# main.net
KiCad netlist of a schematic drawn in EAGLE
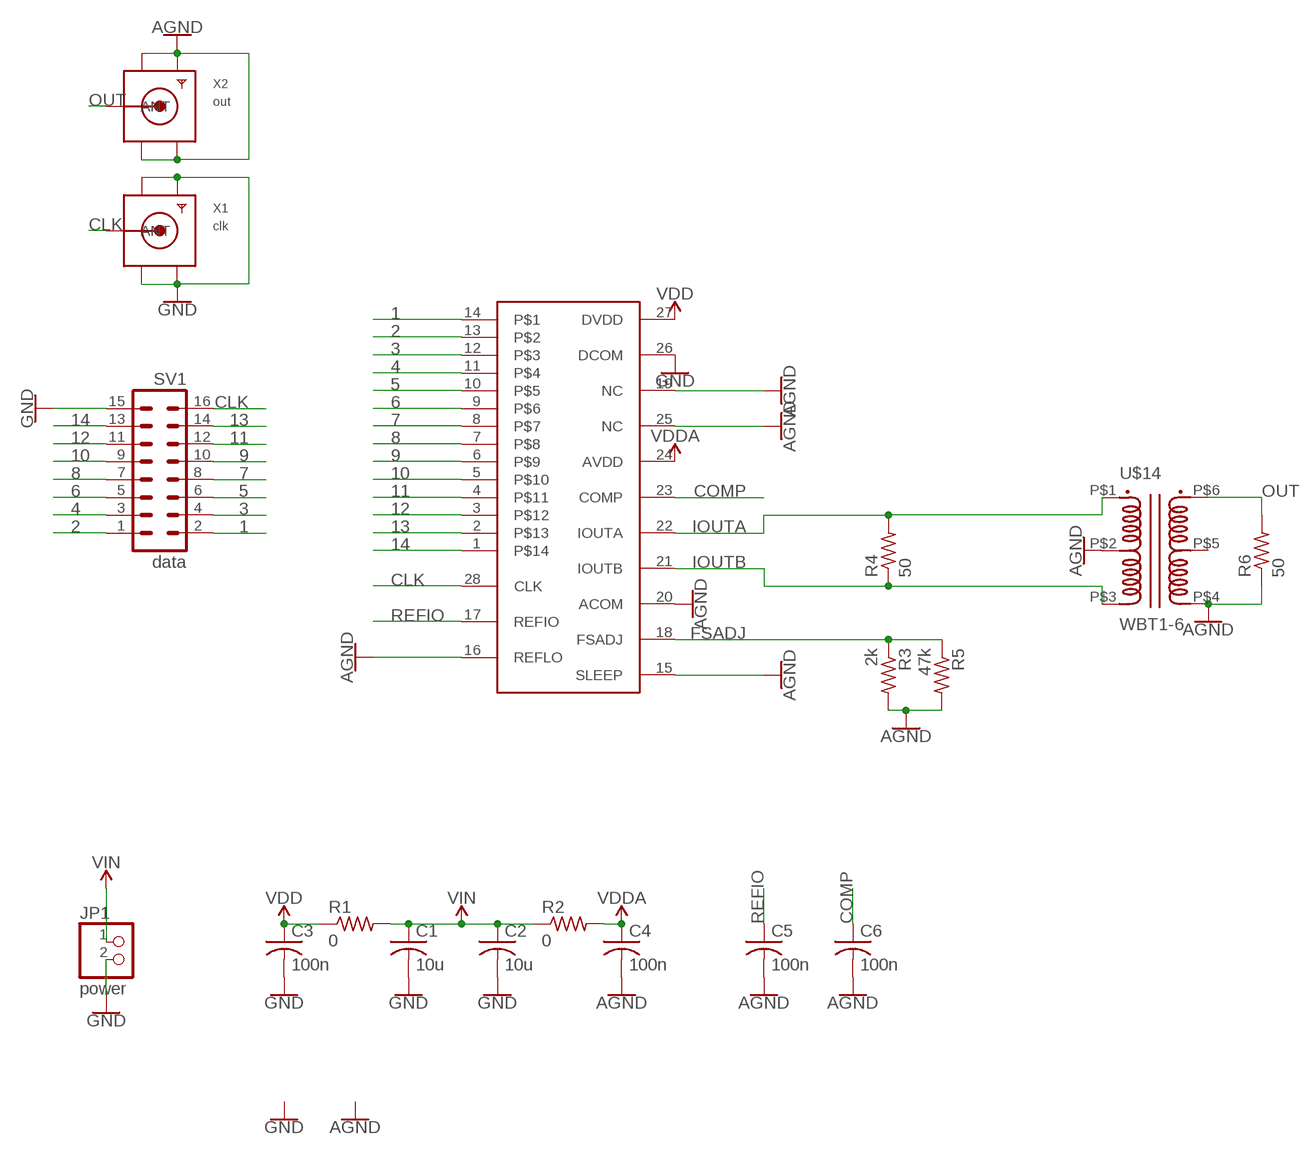
[diagram p0: schematic, sheet 1]

(export (version "E")
  (design (tool "Eeschema 10.0.6"))
  (components
    (comp (ref "C1")
      (value "10u")
      (footprint "eagle-import:C0805K")
      (libsource (lib "eagle-import") (part "C-USC0805K"))
    )
    (comp (ref "C2")
      (value "10u")
      (footprint "eagle-import:C0805K")
      (libsource (lib "eagle-import") (part "C-USC0805K"))
    )
    (comp (ref "C3")
      (value "100n")
      (footprint "eagle-import:C0603K")
      (libsource (lib "eagle-import") (part "C-USC0603K"))
    )
    (comp (ref "C4")
      (value "100n")
      (footprint "eagle-import:C0603K")
      (libsource (lib "eagle-import") (part "C-USC0603K"))
    )
    (comp (ref "C5")
      (value "100n")
      (footprint "eagle-import:C0603K")
      (libsource (lib "eagle-import") (part "C-USC0603K"))
    )
    (comp (ref "C6")
      (value "100n")
      (footprint "eagle-import:C0603K")
      (libsource (lib "eagle-import") (part "C-USC0603K"))
    )
    (comp (ref "JP1")
      (value "power")
      (footprint "eagle-import:1X02")
      (libsource (lib "eagle-import") (part "PINHD-1X2"))
    )
    (comp (ref "R1")
      (value "0")
      (footprint "eagle-import:0309_10")
      (libsource (lib "eagle-import") (part "R-US_0309/10"))
    )
    (comp (ref "R2")
      (value "0")
      (footprint "eagle-import:0309_10")
      (libsource (lib "eagle-import") (part "R-US_0309/10"))
    )
    (comp (ref "R3")
      (value "2k")
      (footprint "eagle-import:R0603")
      (libsource (lib "eagle-import") (part "R-US_R0603"))
    )
    (comp (ref "R4")
      (value "50")
      (footprint "eagle-import:R0603")
      (libsource (lib "eagle-import") (part "R-US_R0603"))
    )
    (comp (ref "R5")
      (value "47k")
      (footprint "eagle-import:R0603")
      (libsource (lib "eagle-import") (part "R-US_R0603"))
    )
    (comp (ref "R6")
      (value "50")
      (footprint "eagle-import:R0603")
      (libsource (lib "eagle-import") (part "R-US_R0603"))
    )
    (comp (ref "SV1")
      (value "data")
      (footprint "eagle-import:MA08-2")
      (libsource (lib "eagle-import") (part "MA08-2"))
    )
    (comp (ref "U$1")
      (value "ISL5961")
      (footprint "eagle-import:TSSOP28")
      (libsource (lib "eagle-import") (part "ISL5961"))
    )
    (comp (ref "U$14")
      (value "WBT1-6")
      (footprint "eagle-import:WBT1-6")
      (libsource (lib "eagle-import") (part "WBT1-6"))
    )
    (comp (ref "X1")
      (value "clk")
      (footprint "eagle-import:SMA_EDGELAUNCH")
      (libsource (lib "eagle-import") (part "SMACONNECTOR_EDGE"))
    )
    (comp (ref "X2")
      (value "out")
      (footprint "eagle-import:SMA_EDGELAUNCH")
      (libsource (lib "eagle-import") (part "SMACONNECTOR_EDGE"))
    )
  )
  (nets
    (net (code "1") (name "/1") (class "Default")
      (node (ref "SV1") (pin "2") (pinfunction "2_2") (pintype "passive"))
      (node (ref "U$1") (pin "14") (pinfunction "P$1_14") (pintype "bidirectional"))
    )
    (net (code "2") (name "/2") (class "Default")
      (node (ref "SV1") (pin "1") (pinfunction "1_1") (pintype "passive"))
      (node (ref "U$1") (pin "13") (pinfunction "P$2_13") (pintype "bidirectional"))
    )
    (net (code "3") (name "/3") (class "Default")
      (node (ref "SV1") (pin "4") (pinfunction "4_4") (pintype "passive"))
      (node (ref "U$1") (pin "12") (pinfunction "P$3_12") (pintype "bidirectional"))
    )
    (net (code "4") (name "/4") (class "Default")
      (node (ref "SV1") (pin "3") (pinfunction "3_3") (pintype "passive"))
      (node (ref "U$1") (pin "11") (pinfunction "P$4_11") (pintype "bidirectional"))
    )
    (net (code "5") (name "/5") (class "Default")
      (node (ref "SV1") (pin "6") (pinfunction "6_6") (pintype "passive"))
      (node (ref "U$1") (pin "10") (pinfunction "P$5_10") (pintype "bidirectional"))
    )
    (net (code "6") (name "/6") (class "Default")
      (node (ref "SV1") (pin "5") (pinfunction "5_5") (pintype "passive"))
      (node (ref "U$1") (pin "9") (pinfunction "P$6_9") (pintype "bidirectional"))
    )
    (net (code "7") (name "/7") (class "Default")
      (node (ref "SV1") (pin "8") (pinfunction "8_8") (pintype "passive"))
      (node (ref "U$1") (pin "8") (pinfunction "P$7_8") (pintype "bidirectional"))
    )
    (net (code "8") (name "/8") (class "Default")
      (node (ref "SV1") (pin "7") (pinfunction "7_7") (pintype "passive"))
      (node (ref "U$1") (pin "7") (pinfunction "P$8_7") (pintype "bidirectional"))
    )
    (net (code "9") (name "/9") (class "Default")
      (node (ref "SV1") (pin "10") (pinfunction "10_10") (pintype "passive"))
      (node (ref "U$1") (pin "6") (pinfunction "P$9_6") (pintype "bidirectional"))
    )
    (net (code "10") (name "/10") (class "Default")
      (node (ref "SV1") (pin "9") (pinfunction "9_9") (pintype "passive"))
      (node (ref "U$1") (pin "5") (pinfunction "P$10_5") (pintype "bidirectional"))
    )
    (net (code "11") (name "/11") (class "Default")
      (node (ref "SV1") (pin "12") (pinfunction "12_12") (pintype "passive"))
      (node (ref "U$1") (pin "4") (pinfunction "P$11_4") (pintype "bidirectional"))
    )
    (net (code "12") (name "/12") (class "Default")
      (node (ref "SV1") (pin "11") (pinfunction "11_11") (pintype "passive"))
      (node (ref "U$1") (pin "3") (pinfunction "P$12_3") (pintype "bidirectional"))
    )
    (net (code "13") (name "/13") (class "Default")
      (node (ref "SV1") (pin "14") (pinfunction "14_14") (pintype "passive"))
      (node (ref "U$1") (pin "2") (pinfunction "P$13_2") (pintype "bidirectional"))
    )
    (net (code "14") (name "/14") (class "Default")
      (node (ref "SV1") (pin "13") (pinfunction "13_13") (pintype "passive"))
      (node (ref "U$1") (pin "1") (pinfunction "P$14_1") (pintype "bidirectional"))
    )
    (net (code "15") (name "/CLK") (class "Default")
      (node (ref "SV1") (pin "16") (pinfunction "16_16") (pintype "passive"))
      (node (ref "U$1") (pin "28") (pinfunction "CLK_28") (pintype "bidirectional"))
      (node (ref "X1") (pin "P") (pinfunction "ANT_P") (pintype "bidirectional"))
    )
    (net (code "16") (name "/COMP") (class "Default")
      (node (ref "C6") (pin "1") (pinfunction "1_1") (pintype "passive"))
      (node (ref "U$1") (pin "23") (pinfunction "COMP_23") (pintype "bidirectional"))
    )
    (net (code "17") (name "/FSADJ") (class "Default")
      (node (ref "R3") (pin "1") (pinfunction "1_1") (pintype "passive"))
      (node (ref "R5") (pin "1") (pinfunction "1_1") (pintype "passive"))
      (node (ref "U$1") (pin "18") (pinfunction "FSADJ_18") (pintype "bidirectional"))
    )
    (net (code "18") (name "/IOUTA") (class "Default")
      (node (ref "R4") (pin "2") (pinfunction "2_2") (pintype "passive"))
      (node (ref "U$1") (pin "22") (pinfunction "IOUTA_22") (pintype "bidirectional"))
      (node (ref "U$14") (pin "P$1") (pinfunction "1A_P$1") (pintype "passive"))
    )
    (net (code "19") (name "/IOUTB") (class "Default")
      (node (ref "R4") (pin "1") (pinfunction "1_1") (pintype "passive"))
      (node (ref "U$1") (pin "21") (pinfunction "IOUTB_21") (pintype "bidirectional"))
      (node (ref "U$14") (pin "P$3") (pinfunction "1B_P$3") (pintype "passive"))
    )
    (net (code "20") (name "/OUT") (class "Default")
      (node (ref "R6") (pin "2") (pinfunction "2_2") (pintype "passive"))
      (node (ref "U$14") (pin "P$6") (pinfunction "2A_P$6") (pintype "passive"))
      (node (ref "X2") (pin "P") (pinfunction "ANT_P") (pintype "bidirectional"))
    )
    (net (code "21") (name "/REFIO") (class "Default")
      (node (ref "C5") (pin "1") (pinfunction "1_1") (pintype "passive"))
      (node (ref "U$1") (pin "17") (pinfunction "REFIO_17") (pintype "bidirectional"))
    )
    (net (code "22") (name "AGND") (class "Default")
      (node (ref "C4") (pin "2") (pinfunction "2_2") (pintype "passive"))
      (node (ref "C5") (pin "2") (pinfunction "2_2") (pintype "passive"))
      (node (ref "C6") (pin "2") (pinfunction "2_2") (pintype "passive"))
      (node (ref "R3") (pin "2") (pinfunction "2_2") (pintype "passive"))
      (node (ref "R5") (pin "2") (pinfunction "2_2") (pintype "passive"))
      (node (ref "R6") (pin "1") (pinfunction "1_1") (pintype "passive"))
      (node (ref "U$1") (pin "15") (pinfunction "SLEEP_15") (pintype "bidirectional"))
      (node (ref "U$1") (pin "16") (pinfunction "REFLO_16") (pintype "bidirectional"))
      (node (ref "U$1") (pin "19") (pinfunction "NC_19") (pintype "bidirectional"))
      (node (ref "U$1") (pin "20") (pinfunction "ACOM_20") (pintype "bidirectional"))
      (node (ref "U$1") (pin "25") (pinfunction "NC_25") (pintype "bidirectional"))
      (node (ref "U$14") (pin "P$2") (pinfunction "1M_P$2") (pintype "passive"))
      (node (ref "U$14") (pin "P$4") (pinfunction "2B_P$4") (pintype "passive"))
      (node (ref "X2") (pin "GND@1") (pinfunction "GND4_GND@1") (pintype "power_in"))
      (node (ref "X2") (pin "GND@2") (pinfunction "GND3_GND@2") (pintype "power_in"))
      (node (ref "X2") (pin "GND@3") (pinfunction "GND2_GND@3") (pintype "power_in"))
      (node (ref "X2") (pin "GND@4") (pinfunction "GND1_GND@4") (pintype "power_in"))
    )
    (net (code "23") (name "GND") (class "Default")
      (node (ref "C1") (pin "2") (pinfunction "2_2") (pintype "passive"))
      (node (ref "C2") (pin "2") (pinfunction "2_2") (pintype "passive"))
      (node (ref "C3") (pin "2") (pinfunction "2_2") (pintype "passive"))
      (node (ref "JP1") (pin "2") (pinfunction "2_2") (pintype "passive"))
      (node (ref "SV1") (pin "15") (pinfunction "15_15") (pintype "passive"))
      (node (ref "U$1") (pin "26") (pinfunction "DCOM_26") (pintype "bidirectional"))
      (node (ref "X1") (pin "GND@1") (pinfunction "GND4_GND@1") (pintype "power_in"))
      (node (ref "X1") (pin "GND@2") (pinfunction "GND3_GND@2") (pintype "power_in"))
      (node (ref "X1") (pin "GND@3") (pinfunction "GND2_GND@3") (pintype "power_in"))
      (node (ref "X1") (pin "GND@4") (pinfunction "GND1_GND@4") (pintype "power_in"))
    )
    (net (code "24") (name "VDD") (class "Default")
      (node (ref "C3") (pin "1") (pinfunction "1_1") (pintype "passive"))
      (node (ref "R1") (pin "1") (pinfunction "1_1") (pintype "passive"))
      (node (ref "U$1") (pin "27") (pinfunction "DVDD_27") (pintype "bidirectional"))
    )
    (net (code "25") (name "VDDA") (class "Default")
      (node (ref "C4") (pin "1") (pinfunction "1_1") (pintype "passive"))
      (node (ref "R2") (pin "2") (pinfunction "2_2") (pintype "passive"))
      (node (ref "U$1") (pin "24") (pinfunction "AVDD_24") (pintype "bidirectional"))
    )
    (net (code "26") (name "VIN") (class "Default")
      (node (ref "C1") (pin "1") (pinfunction "1_1") (pintype "passive"))
      (node (ref "C2") (pin "1") (pinfunction "1_1") (pintype "passive"))
      (node (ref "JP1") (pin "1") (pinfunction "1_1") (pintype "passive"))
      (node (ref "R1") (pin "2") (pinfunction "2_2") (pintype "passive"))
      (node (ref "R2") (pin "1") (pinfunction "1_1") (pintype "passive"))
    )
    (net (code "27") (name "unconnected-(U$14-2M-PadP$5)") (class "Default")
      (node (ref "U$14") (pin "P$5") (pinfunction "2M_P$5") (pintype "passive"))
    )
  )
)
